# 06_POWER_3.net
KiCad netlist of a schematic drawn in Altium Designer
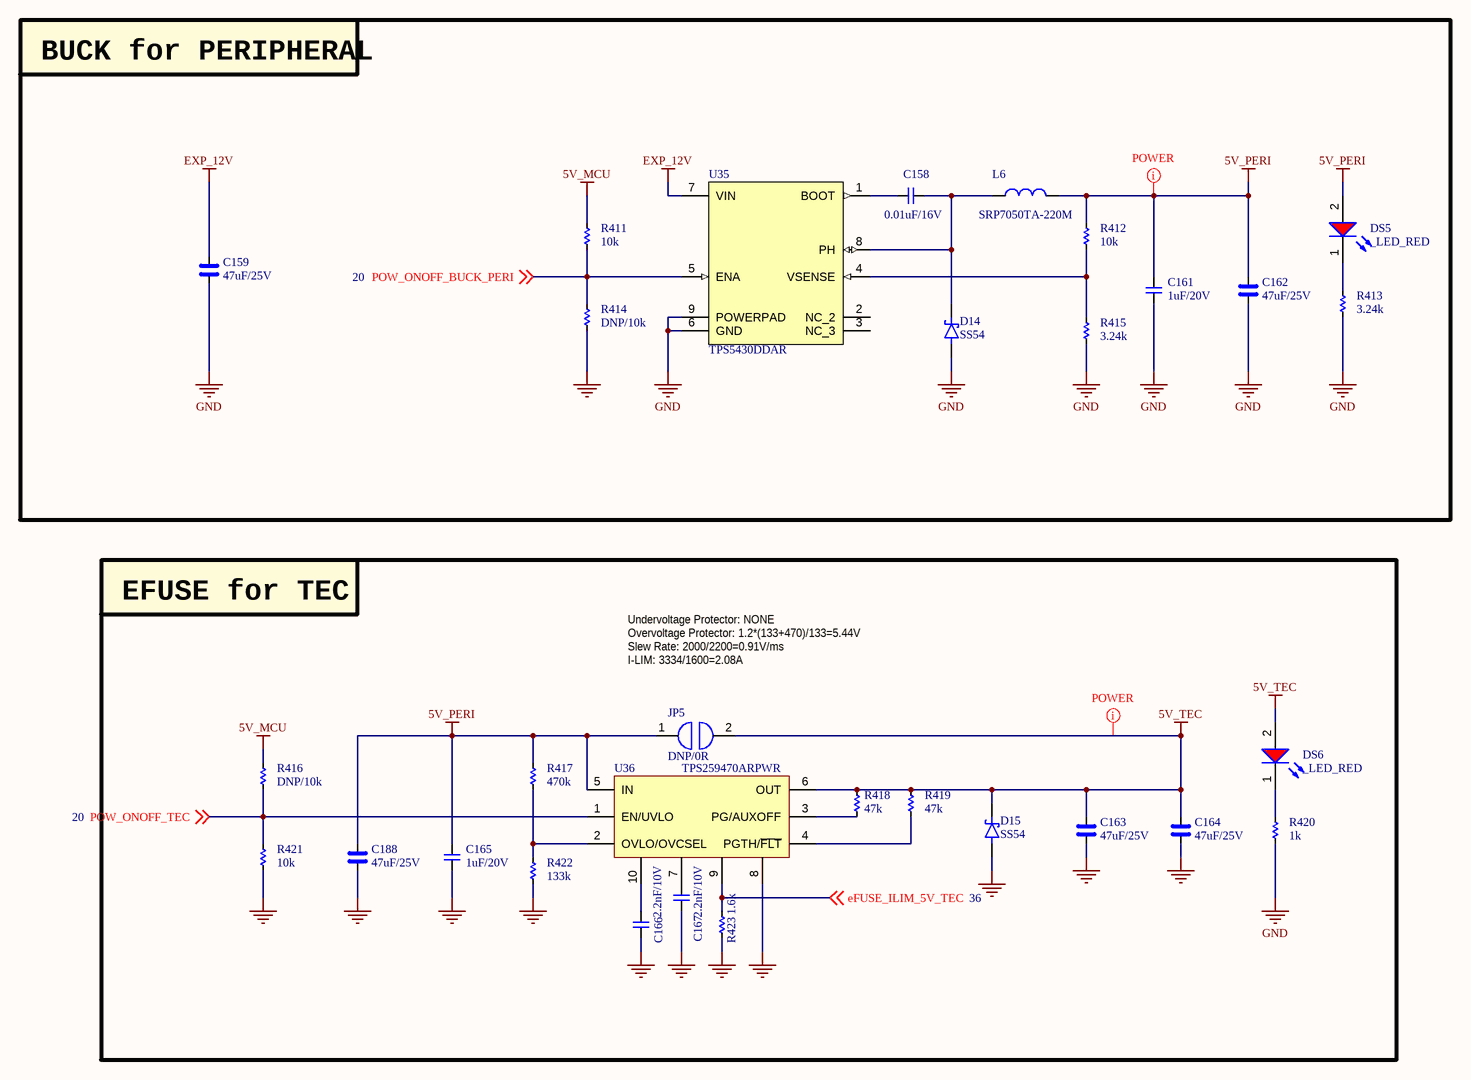
[diagram p0: 06_POWER_3.SchDoc]

(export (version "E")
  (design (tool "Eeschema 10.0.6"))
  (components
    (comp (ref "C158")
      (value "0.01uF/16V")
      (footprint "CAP_C_1608X80")
      (description "CAP")
      (libsource (lib "LABLIB") (part "_CAP_C_2"))
    )
    (comp (ref "C159")
      (value "47uF/25V")
      (footprint "CAP_C_3225X80")
      (description "CAP High Value")
      (libsource (lib "LABLIB") (part "_CAP_C_High_2"))
    )
    (comp (ref "C161")
      (value "1uF/20V")
      (footprint "CAP_C_1005X60")
      (description "CAP")
      (libsource (lib "LABLIB") (part "_CAP_C_2"))
    )
    (comp (ref "C162")
      (value "47uF/25V")
      (footprint "CAP_C_3225X80")
      (description "CAP High Value")
      (libsource (lib "LABLIB") (part "_CAP_C_High_2"))
    )
    (comp (ref "C163")
      (value "47uF/25V")
      (footprint "CAP_C_3225X80")
      (description "CAP High Value")
      (libsource (lib "LABLIB") (part "_CAP_C_High_2"))
    )
    (comp (ref "C164")
      (value "47uF/25V")
      (footprint "CAP_C_3225X80")
      (description "CAP High Value")
      (libsource (lib "LABLIB") (part "_CAP_C_High_2"))
    )
    (comp (ref "C165")
      (value "1uF/20V")
      (footprint "CAP_C_1005X60")
      (description "CAP")
      (libsource (lib "LABLIB") (part "_CAP_C_2"))
    )
    (comp (ref "C166")
      (value "2.2nF/10V")
      (footprint "CAP_C_1005X60")
      (description "CAP")
      (libsource (lib "LABLIB") (part "_CAP_C_2"))
    )
    (comp (ref "C167")
      (value "2.2nF/10V")
      (footprint "CAP_C_1005X60")
      (description "CAP")
      (libsource (lib "LABLIB") (part "_CAP_C_2"))
    )
    (comp (ref "C188")
      (value "47uF/25V")
      (footprint "CAP_C_3225X80")
      (description "CAP High Value")
      (libsource (lib "LABLIB") (part "_CAP_C_High_2"))
    )
    (comp (ref "D14")
      (value "SS54")
      (footprint "DO-214AC_SMA")
      (description "DIODE SCHOTTKY")
      (libsource (lib "LABLIB") (part "DIODE SCHOTTKY"))
    )
    (comp (ref "D15")
      (value "SS54")
      (footprint "DO-214AC_SMA")
      (description "DIODE SCHOTTKY")
      (libsource (lib "LABLIB") (part "DIODE SCHOTTKY"))
    )
    (comp (ref "DS5") (value "_LED_RED") (footprint "LED_0603") (libsource (lib "LABLIB") (part "_LED_RED")))
    (comp (ref "DS6") (value "_LED_RED") (footprint "LED_0603") (libsource (lib "LABLIB") (part "_LED_RED")))
    (comp (ref "JP5") (value "DNP/0R") (footprint "JUMPER_1608") (libsource (lib "EXP_V1") (part "JUMPER")))
    (comp (ref "L6")
      (value "SRP7050TA-220M")
      (footprint "PSM6050")
      (description "FIXED IND 22UH 2.5A 170 MOHM SMD")
      (libsource (lib "LABLIB") (part "SRP7050TA-220M"))
    )
    (comp (ref "R411")
      (value "10k")
      (footprint "RES_C_1005X40")
      (description "RES")
      (libsource (lib "LABLIB") (part "_RES_B_2"))
    )
    (comp (ref "R412")
      (value "10k")
      (footprint "RES_C_1005X40")
      (description "RES")
      (libsource (lib "LABLIB") (part "_RES_B_2"))
    )
    (comp (ref "R413")
      (value "3.24k")
      (footprint "RES_C_1005X40")
      (description "RES")
      (libsource (lib "LABLIB") (part "_RES_B_2"))
    )
    (comp (ref "R414")
      (value "DNP/10k")
      (footprint "RES_C_1005X40")
      (description "RES")
      (libsource (lib "LABLIB") (part "_RES_B_2"))
    )
    (comp (ref "R415")
      (value "3.24k")
      (footprint "RES_C_1005X40")
      (description "RES")
      (libsource (lib "LABLIB") (part "_RES_B_2"))
    )
    (comp (ref "R416")
      (value "DNP/10k")
      (footprint "RES_C_1005X40")
      (description "RES")
      (libsource (lib "LABLIB") (part "_RES_B_2"))
    )
    (comp (ref "R417")
      (value "470k")
      (footprint "RES_C_1005X40")
      (description "RES")
      (libsource (lib "LABLIB") (part "_RES_B_2"))
    )
    (comp (ref "R418")
      (value "47k")
      (footprint "RES_C_1005X40")
      (description "RES")
      (libsource (lib "LABLIB") (part "_RES_B_2"))
    )
    (comp (ref "R419")
      (value "47k")
      (footprint "RES_C_1005X40")
      (description "RES")
      (libsource (lib "LABLIB") (part "_RES_B_2"))
    )
    (comp (ref "R420")
      (value "1k")
      (footprint "RES_C_1005X40")
      (description "RES")
      (libsource (lib "LABLIB") (part "_RES_B_2"))
    )
    (comp (ref "R421")
      (value "10k")
      (footprint "RES_C_1005X40")
      (description "RES")
      (libsource (lib "LABLIB") (part "_RES_B_2"))
    )
    (comp (ref "R422")
      (value "133k")
      (footprint "RES_C_1005X40")
      (description "RES")
      (libsource (lib "LABLIB") (part "_RES_B_2"))
    )
    (comp (ref "R423")
      (value "1.6k")
      (footprint "RES_C_1005X40")
      (description "RES")
      (libsource (lib "LABLIB") (part "_RES_B_2"))
    )
    (comp (ref "U35")
      (value "TPS5430DDAR")
      (footprint "TPS54531DDAR")
      (description "IC REG BUCK ADJ 3A 8SOPWR")
      (libsource (lib "EXP_HW_V3") (part "TPS5430DDAR"))
    )
    (comp (ref "U36")
      (value "TPS259470ARPWR")
      (footprint "VQFN-HR-10")
      (libsource (lib "EXP_HW_V3") (part "TPS259470ARPWR"))
    )
  )
  (nets
    (net (code "1") (name "5V_MCU") (class "Default")
      (node (ref "R411") (pin "1") (pinfunction "1_1") (pintype "passive"))
      (node (ref "R416") (pin "1") (pinfunction "1_1") (pintype "passive"))
    )
    (net (code "2") (name "5V_PERI") (class "Default")
      (node (ref "C161") (pin "2") (pinfunction "2_2") (pintype "passive"))
      (node (ref "C162") (pin "2") (pinfunction "2_2") (pintype "passive"))
      (node (ref "C165") (pin "2") (pinfunction "2_2") (pintype "passive"))
      (node (ref "C188") (pin "2") (pinfunction "2_2") (pintype "passive"))
      (node (ref "DS5") (pin "2") (pinfunction "A_2") (pintype "passive"))
      (node (ref "JP5") (pin "1") (pinfunction "1_1") (pintype "passive"))
      (node (ref "L6") (pin "2") (pinfunction "2_2") (pintype "passive"))
      (node (ref "R412") (pin "2") (pinfunction "2_2") (pintype "passive"))
      (node (ref "R417") (pin "2") (pinfunction "2_2") (pintype "passive"))
      (node (ref "U36") (pin "5") (pinfunction "IN_5") (pintype "passive"))
    )
    (net (code "3") (name "5V_TEC") (class "Default")
      (node (ref "C163") (pin "2") (pinfunction "2_2") (pintype "passive"))
      (node (ref "C164") (pin "2") (pinfunction "2_2") (pintype "passive"))
      (node (ref "D15") (pin "1") (pinfunction "K_1") (pintype "passive"))
      (node (ref "DS6") (pin "2") (pinfunction "A_2") (pintype "passive"))
      (node (ref "JP5") (pin "2") (pinfunction "2_2") (pintype "passive"))
      (node (ref "R418") (pin "2") (pinfunction "2_2") (pintype "passive"))
      (node (ref "R419") (pin "2") (pinfunction "2_2") (pintype "passive"))
      (node (ref "U36") (pin "6") (pinfunction "OUT_6") (pintype "passive"))
    )
    (net (code "4") (name "EXP_12V") (class "Default")
      (node (ref "C159") (pin "2") (pinfunction "2_2") (pintype "passive"))
      (node (ref "U35") (pin "7") (pinfunction "VIN_7") (pintype "power_in"))
    )
    (net (code "5") (name "GND") (class "Default")
      (node (ref "C159") (pin "1") (pinfunction "1_1") (pintype "passive"))
      (node (ref "C161") (pin "1") (pinfunction "1_1") (pintype "passive"))
      (node (ref "C162") (pin "1") (pinfunction "1_1") (pintype "passive"))
      (node (ref "C163") (pin "1") (pinfunction "1_1") (pintype "passive"))
      (node (ref "C164") (pin "1") (pinfunction "1_1") (pintype "passive"))
      (node (ref "C165") (pin "1") (pinfunction "1_1") (pintype "passive"))
      (node (ref "C166") (pin "1") (pinfunction "1_1") (pintype "passive"))
      (node (ref "C167") (pin "1") (pinfunction "1_1") (pintype "passive"))
      (node (ref "C188") (pin "1") (pinfunction "1_1") (pintype "passive"))
      (node (ref "D14") (pin "2") (pinfunction "A_2") (pintype "passive"))
      (node (ref "D15") (pin "2") (pinfunction "A_2") (pintype "passive"))
      (node (ref "R413") (pin "1") (pinfunction "1_1") (pintype "passive"))
      (node (ref "R414") (pin "2") (pinfunction "2_2") (pintype "passive"))
      (node (ref "R415") (pin "1") (pinfunction "1_1") (pintype "passive"))
      (node (ref "R420") (pin "1") (pinfunction "1_1") (pintype "passive"))
      (node (ref "R421") (pin "2") (pinfunction "2_2") (pintype "passive"))
      (node (ref "R422") (pin "1") (pinfunction "1_1") (pintype "passive"))
      (node (ref "R423") (pin "1") (pinfunction "1_1") (pintype "passive"))
      (node (ref "U35") (pin "6") (pinfunction "GND_6") (pintype "power_in"))
      (node (ref "U35") (pin "9") (pinfunction "POWERPAD_9") (pintype "power_in"))
      (node (ref "U36") (pin "8") (pinfunction "8_8") (pintype "passive"))
    )
    (net (code "6") (name "Net-(C166-Pad2)") (class "Default")
      (node (ref "C166") (pin "2") (pinfunction "2_2") (pintype "passive"))
      (node (ref "U36") (pin "10") (pinfunction "10_10") (pintype "passive"))
    )
    (net (code "7") (name "Net-(C167-Pad2)") (class "Default")
      (node (ref "C167") (pin "2") (pinfunction "2_2") (pintype "passive"))
      (node (ref "U36") (pin "7") (pinfunction "7_7") (pintype "passive"))
    )
    (net (code "8") (name "Net-(D14-K)") (class "Default")
      (node (ref "C158") (pin "1") (pinfunction "1_1") (pintype "passive"))
      (node (ref "D14") (pin "1") (pinfunction "K_1") (pintype "passive"))
      (node (ref "L6") (pin "1") (pinfunction "1_1") (pintype "passive"))
      (node (ref "U35") (pin "8") (pinfunction "PH_8") (pintype "bidirectional"))
    )
    (net (code "9") (name "Net-(DS5-K)") (class "Default")
      (node (ref "DS5") (pin "1") (pinfunction "K_1") (pintype "passive"))
      (node (ref "R413") (pin "2") (pinfunction "2_2") (pintype "passive"))
    )
    (net (code "10") (name "Net-(DS6-K)") (class "Default")
      (node (ref "DS6") (pin "1") (pinfunction "K_1") (pintype "passive"))
      (node (ref "R420") (pin "2") (pinfunction "2_2") (pintype "passive"))
    )
    (net (code "11") (name "Net-(U35-BOOT)") (class "Default")
      (node (ref "C158") (pin "2") (pinfunction "2_2") (pintype "passive"))
      (node (ref "U35") (pin "1") (pinfunction "BOOT_1") (pintype "output"))
    )
    (net (code "12") (name "Net-(U35-VSENSE)") (class "Default")
      (node (ref "R412") (pin "1") (pinfunction "1_1") (pintype "passive"))
      (node (ref "R415") (pin "2") (pinfunction "2_2") (pintype "passive"))
      (node (ref "U35") (pin "4") (pinfunction "VSENSE_4") (pintype "input"))
    )
    (net (code "13") (name "Net-(U36-OVLO{slash}OVCSEL)") (class "Default")
      (node (ref "R417") (pin "1") (pinfunction "1_1") (pintype "passive"))
      (node (ref "R422") (pin "2") (pinfunction "2_2") (pintype "passive"))
      (node (ref "U36") (pin "2") (pinfunction "OVLO/OVCSEL_2") (pintype "passive"))
    )
    (net (code "14") (name "Net-(U36-PGTH{slash}~{FLT})") (class "Default")
      (node (ref "R419") (pin "1") (pinfunction "1_1") (pintype "passive"))
      (node (ref "U36") (pin "4") (pinfunction "PGTH/~{FLT}_4") (pintype "passive"))
    )
    (net (code "15") (name "Net-(U36-PG{slash}AUXOFF)") (class "Default")
      (node (ref "R418") (pin "1") (pinfunction "1_1") (pintype "passive"))
      (node (ref "U36") (pin "3") (pinfunction "PG/AUXOFF_3") (pintype "passive"))
    )
    (net (code "16") (name "POW_ONOFF_BUCK_PERI") (class "Default")
      (node (ref "R411") (pin "2") (pinfunction "2_2") (pintype "passive"))
      (node (ref "R414") (pin "1") (pinfunction "1_1") (pintype "passive"))
      (node (ref "U35") (pin "5") (pinfunction "ENA_5") (pintype "input"))
    )
    (net (code "17") (name "POW_ONOFF_TEC") (class "Default")
      (node (ref "R416") (pin "2") (pinfunction "2_2") (pintype "passive"))
      (node (ref "R421") (pin "1") (pinfunction "1_1") (pintype "passive"))
      (node (ref "U36") (pin "1") (pinfunction "EN/UVLO_1") (pintype "passive"))
    )
    (net (code "18") (name "eFUSE_ILIM_5V_TEC") (class "Default")
      (node (ref "R423") (pin "2") (pinfunction "2_2") (pintype "passive"))
      (node (ref "U36") (pin "9") (pinfunction "9_9") (pintype "passive"))
    )
    (net (code "19") (name "unconnected-(U35-NC_2-Pad2)") (class "Default")
      (node (ref "U35") (pin "2") (pinfunction "NC_2_2") (pintype "passive"))
    )
    (net (code "20") (name "unconnected-(U35-NC_3-Pad3)") (class "Default")
      (node (ref "U35") (pin "3") (pinfunction "NC_3_3") (pintype "passive"))
    )
  )
)
